# CAN_Module.net
KiCad netlist of a schematic drawn in Altium Designer
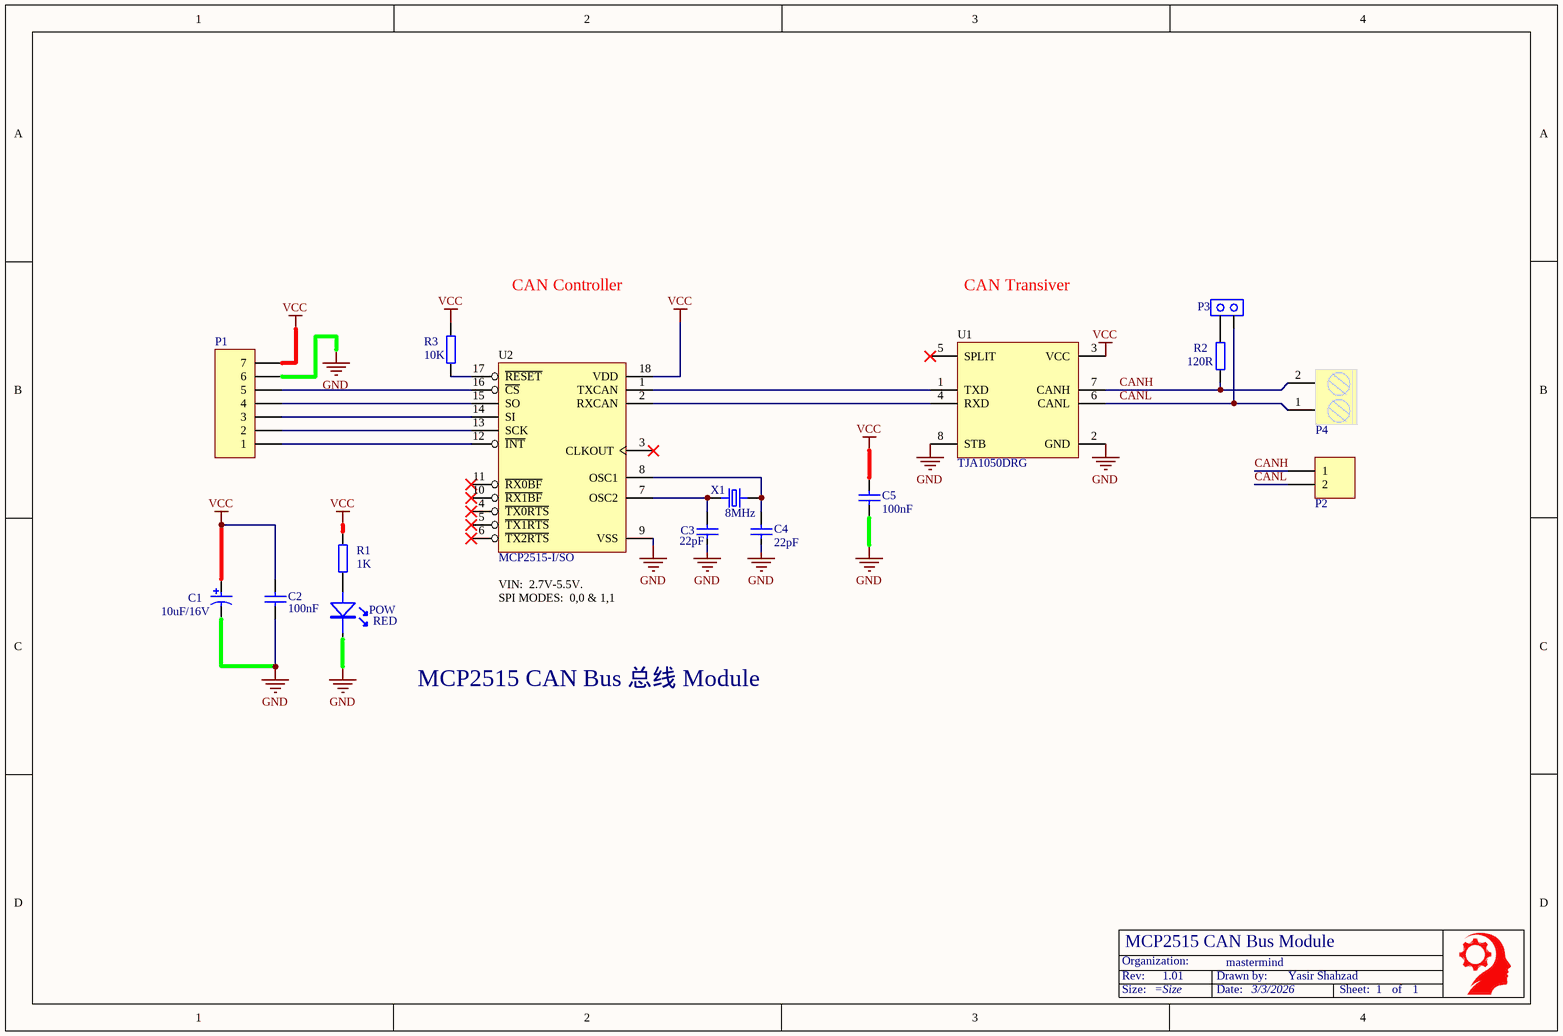
[diagram p0: CAN_Module.SchDoc]

(export (version "E")
  (design (tool "Eeschema 10.0.6"))
  (components
    (comp (ref "*")
      (value "TitleBlock")
      (description "Title Block for Schematic Sheets")
      (libsource (lib "Mastermind Devices") (part "TitleBlock"))
    )
    (comp (ref "C1")
      (value "10uF/16V")
      (footprint "tantalum  A")
      (description "SMD Tantalum Capacitor")
      (libsource (lib "Mastermind Devices") (part "Cap_Tantalum"))
    )
    (comp (ref "C2")
      (value "100nF")
      (footprint "C0603")
      (description "CAP CER 100nF 10V X7R 0603")
      (libsource (lib "Mastermind Devices") (part "Cap_0603"))
    )
    (comp (ref "C3")
      (value "22pF")
      (footprint "C0603")
      (description "CAP CER 22pF 10V X7R 0603")
      (libsource (lib "Mastermind Devices") (part "Cap_0603"))
    )
    (comp (ref "C4")
      (value "22pF")
      (footprint "C0603")
      (description "CAP CER 22pF 10V X7R 0603")
      (libsource (lib "Mastermind Devices") (part "Cap_0603"))
    )
    (comp (ref "C5")
      (value "100nF")
      (footprint "C0603")
      (description "CAP CER 100nF 10V X7R 0603")
      (libsource (lib "Mastermind Devices") (part "Cap_0603"))
    )
    (comp (ref "P1")
      (value "Header 7")
      (footprint "HDR1X7")
      (description "Header, 7-Pin")
      (fields (field (name "PUBLISHER") "Altium Limited"))
      (libsource (lib "Miscellaneous Connectors") (part "Header 7"))
    )
    (comp (ref "P2")
      (value "Header 2")
      (footprint "HDR1X2")
      (description "Header, 2-Pin")
      (fields (field (name "PUBLISHER") "Altium Limited"))
      (libsource (lib "adafruit") (part "Header 2"))
    )
    (comp (ref "P3")
      (value "Header 2")
      (footprint "HDR1X2")
      (description "Header, 2-Pin")
      (fields (field (name "PUBLISHER") "Altium Limited"))
      (libsource (lib "CAN_Project") (part "Header 2_J"))
    )
    (comp (ref "P4")
      (value "Terminal Block 3.5mmPitch: 3,5 mmNumber of pins: 2Created by Rembrandt Electronicswww.rembrandtelectronics.com")
      (footprint "TERMINAL-BLOCK-2-PIN-3.5MM-ROUND-PAD")
      (description "Screw Terminal 3.5mm")
      (libsource (lib "CAN_Project") (part "TERMINAL-3.50-2P"))
    )
    (comp (ref "POW")
      (value "RED")
      (footprint "CHIPLED_0603")
      (description "SMD lamp beads")
      (libsource (lib "CAN_Project") (part "LEDCHIP-LED0603"))
    )
    (comp (ref "R1")
      (value "1K")
      (footprint "R0603")
      (description "RES SMD 1K OHM 1% 1/10W 0603")
      (libsource (lib "") (part "Res_0603_1"))
    )
    (comp (ref "R2")
      (value "120R")
      (footprint "R0603")
      (description "RES SMD 120 OHM 1% 1/10W 0603")
      (libsource (lib "Mastermind Devices") (part "Res_0603"))
    )
    (comp (ref "R3")
      (value "10K")
      (footprint "R0603")
      (description "RES SMD 10K OHM 1% 1/10W 0603")
      (libsource (lib "Mastermind Devices") (part "Res_0603"))
    )
    (comp (ref "U1")
      (value "TJA1050DRG")
      (footprint "SOIC-8E")
      (description "CAN Transiver")
      (fields (field (name "MANUFACTURER") "HGC(深圳汉芯)"))
      (libsource (lib "CAN_Project") (part "TJA1050DRG"))
    )
    (comp (ref "U2")
      (value "MCP2515-I/SO")
      (footprint "SOIC-18_L11.6-W7.5-P1.27-LS10.3-BL")
      (description "CAN Controller")
      (fields (field (name "MANUFACTURER") "Tokmas(托克马斯)") (field (name "MANUFACTURER PART") "MCP2515-I"))
      (libsource (lib "CAN_Project") (part "MCP2515"))
    )
    (comp (ref "X1")
      (value "8MHz")
      (footprint "HC-49US_L11.5-W4.5-P4.88")
      (description "8MHz Â±30ppm Crystal 20pF 60 Ohms HC-49/US")
      (fields (field (name "MP") "ECS-100-20-5PVX") (field (name "MF") "ECS Inc."))
      (libsource (lib "adafruit") (part "CRYSTAL-ECS-100-20-5PVX"))
    )
  )
  (nets
    (net (code "1") (name "/CANH") (class "Default")
      (node (ref "P2") (pin "1") (pinfunction "1_1") (pintype "passive"))
      (node (ref "P4") (pin "2") (pinfunction "2_2") (pintype "passive"))
      (node (ref "R2") (pin "1") (pinfunction "1_1") (pintype "passive"))
      (node (ref "U1") (pin "7") (pinfunction "CANH_7") (pintype "passive"))
    )
    (net (code "2") (name "/CANL") (class "Default")
      (node (ref "P2") (pin "2") (pinfunction "2_2") (pintype "passive"))
      (node (ref "P3") (pin "1") (pinfunction "1_1") (pintype "passive"))
      (node (ref "P4") (pin "1") (pinfunction "1_1") (pintype "passive"))
      (node (ref "U1") (pin "6") (pinfunction "CANL_6") (pintype "passive"))
    )
    (net (code "3") (name "GND") (class "Default")
      (node (ref "C1") (pin "2") (pinfunction "2_2") (pintype "passive"))
      (node (ref "C2") (pin "1") (pinfunction "1_1") (pintype "passive"))
      (node (ref "C3") (pin "2") (pinfunction "2_2") (pintype "passive"))
      (node (ref "C4") (pin "2") (pinfunction "2_2") (pintype "passive"))
      (node (ref "C5") (pin "1") (pinfunction "1_1") (pintype "passive"))
      (node (ref "P1") (pin "6") (pinfunction "6_6") (pintype "passive"))
      (node (ref "POW") (pin "C") (pinfunction "K_C") (pintype "passive"))
      (node (ref "U1") (pin "2") (pinfunction "GND_2") (pintype "passive"))
      (node (ref "U1") (pin "8") (pinfunction "STB_8") (pintype "passive"))
      (node (ref "U2") (pin "9") (pinfunction "VSS_9") (pintype "passive"))
    )
    (net (code "4") (name "Net-(P3-Pad2)") (class "Default")
      (node (ref "P3") (pin "2") (pinfunction "2_2") (pintype "passive"))
      (node (ref "R2") (pin "2") (pinfunction "2_2") (pintype "passive"))
    )
    (net (code "5") (name "Net-(POW-PadA)") (class "Default")
      (node (ref "POW") (pin "A") (pinfunction "A_A") (pintype "passive"))
      (node (ref "R1") (pin "2") (pinfunction "2_2") (pintype "passive"))
    )
    (net (code "6") (name "Net-(U1-RXD)") (class "Default")
      (node (ref "U1") (pin "4") (pinfunction "RXD_4") (pintype "passive"))
      (node (ref "U2") (pin "2") (pinfunction "RXCAN_2") (pintype "passive"))
    )
    (net (code "7") (name "Net-(U1-TXD)") (class "Default")
      (node (ref "U1") (pin "1") (pinfunction "TXD_1") (pintype "passive"))
      (node (ref "U2") (pin "1") (pinfunction "TXCAN_1") (pintype "passive"))
    )
    (net (code "8") (name "Net-(U2-OSC1)") (class "Default")
      (node (ref "C4") (pin "1") (pinfunction "1_1") (pintype "passive"))
      (node (ref "U2") (pin "8") (pinfunction "OSC1_8") (pintype "passive"))
      (node (ref "X1") (pin "1") (pinfunction "1_1") (pintype "passive"))
    )
    (net (code "9") (name "Net-(U2-OSC2)") (class "Default")
      (node (ref "C3") (pin "1") (pinfunction "1_1") (pintype "passive"))
      (node (ref "U2") (pin "7") (pinfunction "OSC2_7") (pintype "passive"))
      (node (ref "X1") (pin "2") (pinfunction "2_2") (pintype "passive"))
    )
    (net (code "10") (name "Net-(U2-SCK)") (class "Default")
      (node (ref "P1") (pin "2") (pinfunction "2_2") (pintype "passive"))
      (node (ref "U2") (pin "13") (pinfunction "SCK_13") (pintype "passive"))
    )
    (net (code "11") (name "Net-(U2-SI)") (class "Default")
      (node (ref "P1") (pin "3") (pinfunction "3_3") (pintype "passive"))
      (node (ref "U2") (pin "14") (pinfunction "SI_14") (pintype "passive"))
    )
    (net (code "12") (name "Net-(U2-SO)") (class "Default")
      (node (ref "P1") (pin "4") (pinfunction "4_4") (pintype "passive"))
      (node (ref "U2") (pin "15") (pinfunction "SO_15") (pintype "passive"))
    )
    (net (code "13") (name "Net-(U2-~{CS})") (class "Default")
      (node (ref "P1") (pin "5") (pinfunction "5_5") (pintype "passive"))
      (node (ref "U2") (pin "16") (pinfunction "~{CS}_16") (pintype "passive"))
    )
    (net (code "14") (name "Net-(U2-~{INT})") (class "Default")
      (node (ref "P1") (pin "1") (pinfunction "1_1") (pintype "passive"))
      (node (ref "U2") (pin "12") (pinfunction "~{INT}_12") (pintype "passive"))
    )
    (net (code "15") (name "Net-(U2-~{RESET})") (class "Default")
      (node (ref "R3") (pin "1") (pinfunction "1_1") (pintype "passive"))
      (node (ref "U2") (pin "17") (pinfunction "~{RESET}_17") (pintype "passive"))
    )
    (net (code "16") (name "VCC") (class "Default")
      (node (ref "C1") (pin "1") (pinfunction "1_1") (pintype "passive"))
      (node (ref "C2") (pin "2") (pinfunction "2_2") (pintype "passive"))
      (node (ref "C5") (pin "2") (pinfunction "2_2") (pintype "passive"))
      (node (ref "P1") (pin "7") (pinfunction "7_7") (pintype "passive"))
      (node (ref "R1") (pin "1") (pinfunction "1_1") (pintype "passive"))
      (node (ref "R3") (pin "2") (pinfunction "2_2") (pintype "passive"))
      (node (ref "U1") (pin "3") (pinfunction "VCC_3") (pintype "passive"))
      (node (ref "U2") (pin "18") (pinfunction "VDD_18") (pintype "passive"))
    )
    (net (code "17") (name "unconnected-(U1-SPLIT-Pad5)") (class "Default")
      (node (ref "U1") (pin "5") (pinfunction "SPLIT_5") (pintype "passive+no_connect"))
    )
    (net (code "18") (name "unconnected-(U2-CLKOUT-Pad3)") (class "Default")
      (node (ref "U2") (pin "3") (pinfunction "CLKOUT_3") (pintype "passive+no_connect"))
    )
    (net (code "19") (name "unconnected-(U2-~{RX0BF}-Pad11)") (class "Default")
      (node (ref "U2") (pin "11") (pinfunction "~{RX0BF}_11") (pintype "passive+no_connect"))
    )
    (net (code "20") (name "unconnected-(U2-~{RX1BF}-Pad10)") (class "Default")
      (node (ref "U2") (pin "10") (pinfunction "~{RX1BF}_10") (pintype "passive+no_connect"))
    )
    (net (code "21") (name "unconnected-(U2-~{TX0RTS}-Pad4)") (class "Default")
      (node (ref "U2") (pin "4") (pinfunction "~{TX0RTS}_4") (pintype "passive+no_connect"))
    )
    (net (code "22") (name "unconnected-(U2-~{TX1RTS}-Pad5)") (class "Default")
      (node (ref "U2") (pin "5") (pinfunction "~{TX1RTS}_5") (pintype "passive+no_connect"))
    )
    (net (code "23") (name "unconnected-(U2-~{TX2RTS}-Pad6)") (class "Default")
      (node (ref "U2") (pin "6") (pinfunction "~{TX2RTS}_6") (pintype "passive+no_connect"))
    )
  )
)
